# SparkFun_Micro_Temperature_Sensor-STTS22.net
KiCad netlist of a schematic drawn in EAGLE
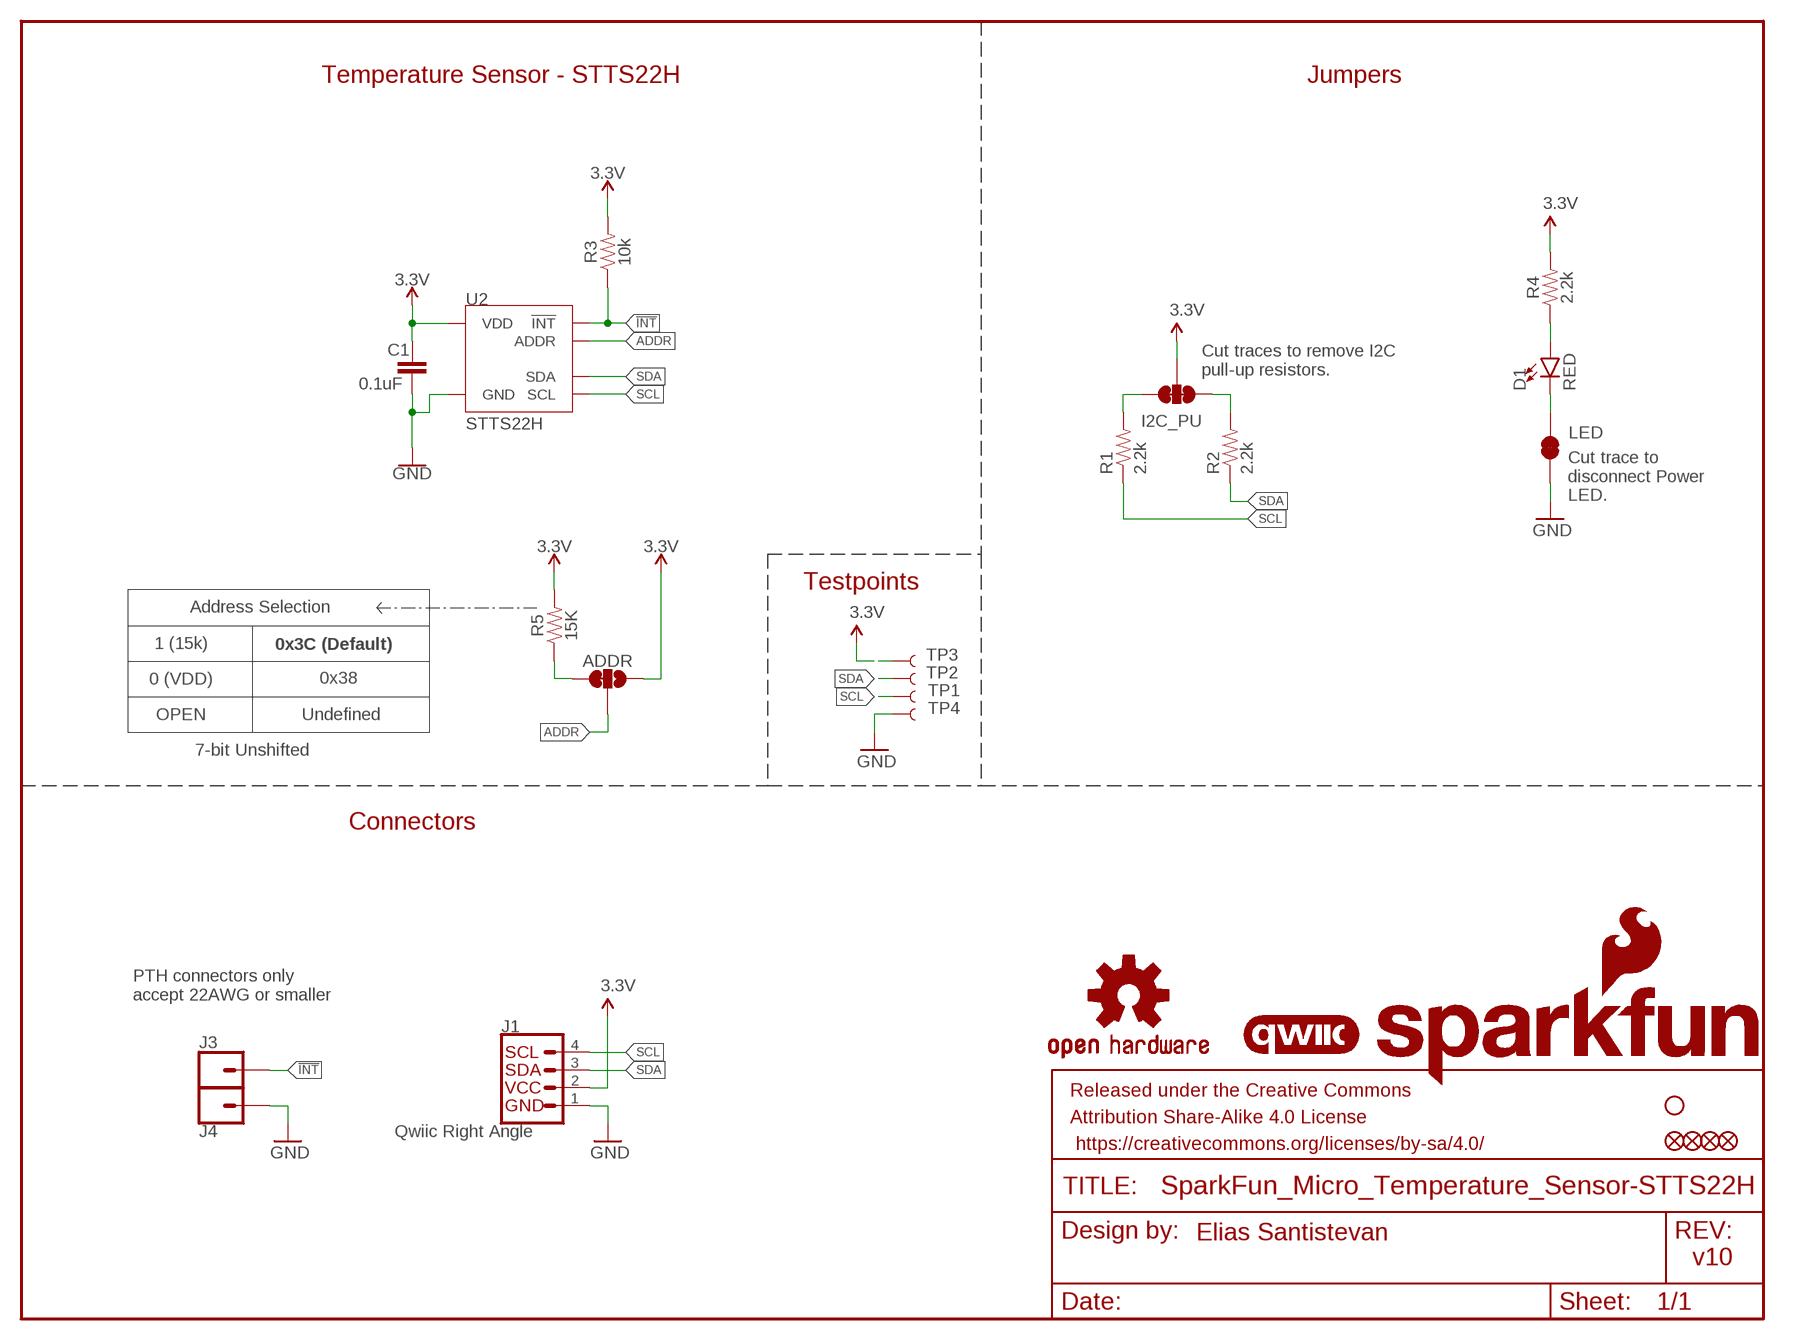
[diagram p0: schematic, sheet 1]

(export (version "E")
  (design (tool "Eeschema 10.0.6"))
  (components
    (comp (ref "ADDR")
      (value "JUMPER-SMT_3_1-NC_TRACE_SILK")
      (footprint "eagle-import:SMT-JUMPER_3_1-NC_TRACE_SILK")
      (libsource (lib "eagle-import") (part "JUMPER-SMT_3_1-NC_TRACE_SILK"))
    )
    (comp (ref "C1")
      (value "0.1uF")
      (footprint "eagle-import:0402-TIGHT")
      (libsource (lib "eagle-import") (part "0.1UF-0402T-16V-10%"))
    )
    (comp (ref "D1")
      (value "RED")
      (footprint "eagle-import:LED-0402")
      (libsource (lib "eagle-import") (part "LED-RED_0402"))
    )
    (comp (ref "FD1")
      (value "FIDUCIALUFIDUCIAL")
      (footprint "eagle-import:FIDUCIAL-MICRO")
      (libsource (lib "eagle-import") (part "FIDUCIALUFIDUCIAL"))
    )
    (comp (ref "FD2")
      (value "FIDUCIALUFIDUCIAL")
      (footprint "eagle-import:FIDUCIAL-MICRO")
      (libsource (lib "eagle-import") (part "FIDUCIALUFIDUCIAL"))
    )
    (comp (ref "FID1")
      (value "FIDUCIALUFIDUCIAL")
      (footprint "eagle-import:FIDUCIAL-MICRO")
      (libsource (lib "eagle-import") (part "FIDUCIALUFIDUCIAL"))
    )
    (comp (ref "FID2")
      (value "FIDUCIALUFIDUCIAL")
      (footprint "eagle-import:FIDUCIAL-MICRO")
      (libsource (lib "eagle-import") (part "FIDUCIALUFIDUCIAL"))
    )
    (comp (ref "FRAME1")
      (value "FRAME-LETTER")
      (footprint "eagle-import:CREATIVE_COMMONS")
      (fields (field (name "DESIGNER") "Elias Santistevan"))
      (libsource (lib "eagle-import") (part "FRAME-LETTER"))
    )
    (comp (ref "I2C_PU")
      (value "S_MODE")
      (footprint "eagle-import:SMT-JUMPER_3_2-NC_TRACE_SILK")
      (libsource (lib "eagle-import") (part "JUMPER-SMT_3_2-NC_TRACE_SILK"))
    )
    (comp (ref "J1")
      (value "Qwiic Right Angle")
      (footprint "eagle-import:JST04_1MM_RA")
      (libsource (lib "eagle-import") (part "I2C_STANDARDQWIIC"))
    )
    (comp (ref "J3")
      (value "CONN_01_1MM")
      (footprint "eagle-import:1X01_1MM_NO_SILK")
      (libsource (lib "eagle-import") (part "CONN_01_1MM"))
    )
    (comp (ref "J4")
      (value "CONN_01_1MM")
      (footprint "eagle-import:1X01_1MM_NO_SILK")
      (libsource (lib "eagle-import") (part "CONN_01_1MM"))
    )
    (comp (ref "LED")
      (value "JUMPER-SMT_2_NC_TRACE_SILK")
      (footprint "eagle-import:SMT-JUMPER_2_NC_TRACE_SILK")
      (libsource (lib "eagle-import") (part "JUMPER-SMT_2_NC_TRACE_SILK"))
    )
    (comp (ref "LOGO1")
      (value "QWIIC_LOGO_3MM")
      (footprint "eagle-import:QWIIC_3MM")
      (libsource (lib "eagle-import") (part "QWIIC_LOGO_3MM"))
    )
    (comp (ref "LOGO2")
      (value "OSHW-LOGOMINI")
      (footprint "eagle-import:OSHW-LOGO-MINI")
      (libsource (lib "eagle-import") (part "OSHW-LOGOMINI"))
    )
    (comp (ref "LOGO3")
      (value "SFE_LOGO_NAME_FLAMEBLANK")
      (footprint "eagle-import:BLANK")
      (libsource (lib "eagle-import") (part "SFE_LOGO_NAME_FLAMEBLANK"))
    )
    (comp (ref "R1")
      (value "2.2k")
      (footprint "eagle-import:0402-TIGHT")
      (libsource (lib "eagle-import") (part "2.2KOHM-0402T-1/16W-1%"))
    )
    (comp (ref "R2")
      (value "2.2k")
      (footprint "eagle-import:0402-TIGHT")
      (libsource (lib "eagle-import") (part "2.2KOHM-0402T-1/16W-1%"))
    )
    (comp (ref "R3")
      (value "10k")
      (footprint "eagle-import:0402-TIGHT")
      (libsource (lib "eagle-import") (part "10KOHM-0402T-1/16W-1%"))
    )
    (comp (ref "R4")
      (value "2.2k")
      (footprint "eagle-import:0402-TIGHT")
      (libsource (lib "eagle-import") (part "2.2KOHM-0402T-1/16W-1%"))
    )
    (comp (ref "R5")
      (value "15K")
      (footprint "eagle-import:0402-TIGHT")
      (libsource (lib "eagle-import") (part "15KOHM-0402-TIGHT-1/16THW-1%"))
    )
    (comp (ref "STANDOFF1")
      (value "STAND-OFFTIGHT")
      (footprint "eagle-import:STAND-OFF-TIGHT")
      (libsource (lib "eagle-import") (part "STAND-OFFTIGHT"))
    )
    (comp (ref "TP1")
      (value "TEST-POINT3")
      (footprint "eagle-import:PAD.03X.03")
      (libsource (lib "eagle-import") (part "TEST-POINT3"))
    )
    (comp (ref "TP2")
      (value "TEST-POINT3")
      (footprint "eagle-import:PAD.03X.03")
      (libsource (lib "eagle-import") (part "TEST-POINT3"))
    )
    (comp (ref "TP3")
      (value "TEST-POINT3")
      (footprint "eagle-import:PAD.03X.03")
      (libsource (lib "eagle-import") (part "TEST-POINT3"))
    )
    (comp (ref "TP4")
      (value "TEST-POINT3")
      (footprint "eagle-import:PAD.03X.03")
      (libsource (lib "eagle-import") (part "TEST-POINT3"))
    )
    (comp (ref "U2")
      (value "STTS22H")
      (footprint "eagle-import:UDFN-6L")
      (libsource (lib "eagle-import") (part "STTS22H"))
    )
  )
  (nets
    (net (code "1") (name "/~{INT}") (class "Default")
      (node (ref "J3") (pin "1") (pinfunction "1_1") (pintype "passive"))
      (node (ref "R3") (pin "1") (pinfunction "1_1") (pintype "passive"))
      (node (ref "U2") (pin "P2") (pinfunction "~{INT}_P2") (pintype "bidirectional"))
    )
    (net (code "2") (name "3.3V") (class "Default")
      (node (ref "ADDR") (pin "1") (pinfunction "1_1") (pintype "passive"))
      (node (ref "C1") (pin "1") (pinfunction "1_1") (pintype "passive"))
      (node (ref "I2C_PU") (pin "2") (pinfunction "2_2") (pintype "passive"))
      (node (ref "J1") (pin "2") (pinfunction "2_2") (pintype "power_in"))
      (node (ref "R3") (pin "2") (pinfunction "2_2") (pintype "passive"))
      (node (ref "R4") (pin "2") (pinfunction "2_2") (pintype "passive"))
      (node (ref "R5") (pin "2") (pinfunction "2_2") (pintype "passive"))
      (node (ref "TP3") (pin "1") (pinfunction "1_1") (pintype "bidirectional"))
      (node (ref "U2") (pin "P3") (pinfunction "VDD_P3") (pintype "power_in"))
    )
    (net (code "3") (name "ADDR") (class "Default")
      (node (ref "ADDR") (pin "2") (pinfunction "2_2") (pintype "passive"))
      (node (ref "U2") (pin "P4") (pinfunction "ADDR_P4") (pintype "bidirectional"))
    )
    (net (code "4") (name "GND") (class "Default")
      (node (ref "C1") (pin "2") (pinfunction "2_2") (pintype "passive"))
      (node (ref "J1") (pin "1") (pinfunction "1_1") (pintype "power_in"))
      (node (ref "J4") (pin "1") (pinfunction "1_1") (pintype "passive"))
      (node (ref "LED") (pin "1") (pinfunction "1_1") (pintype "passive"))
      (node (ref "TP4") (pin "1") (pinfunction "1_1") (pintype "bidirectional"))
      (node (ref "U2") (pin "P5") (pinfunction "GND_P5") (pintype "power_in"))
      (node (ref "U2") (pin "P7") (pinfunction "GND_P7") (pintype "power_in"))
    )
    (net (code "5") (name "Net-(ADDR-Pad3)") (class "Default")
      (node (ref "ADDR") (pin "3") (pinfunction "3_3") (pintype "passive"))
      (node (ref "R5") (pin "1") (pinfunction "1_1") (pintype "passive"))
    )
    (net (code "6") (name "Net-(D1-PadA)") (class "Default")
      (node (ref "D1") (pin "A") (pinfunction "A_A") (pintype "passive"))
      (node (ref "R4") (pin "1") (pinfunction "1_1") (pintype "passive"))
    )
    (net (code "7") (name "Net-(D1-PadC)") (class "Default")
      (node (ref "D1") (pin "C") (pinfunction "C_C") (pintype "passive"))
      (node (ref "LED") (pin "2") (pinfunction "2_2") (pintype "passive"))
    )
    (net (code "8") (name "Net-(I2C_PU-Pad1)") (class "Default")
      (node (ref "I2C_PU") (pin "1") (pinfunction "1_1") (pintype "passive"))
      (node (ref "R1") (pin "2") (pinfunction "2_2") (pintype "passive"))
    )
    (net (code "9") (name "Net-(I2C_PU-Pad3)") (class "Default")
      (node (ref "I2C_PU") (pin "3") (pinfunction "3_3") (pintype "passive"))
      (node (ref "R2") (pin "2") (pinfunction "2_2") (pintype "passive"))
    )
    (net (code "10") (name "SCL") (class "Default")
      (node (ref "J1") (pin "4") (pinfunction "4_4") (pintype "passive"))
      (node (ref "R1") (pin "1") (pinfunction "1_1") (pintype "passive"))
      (node (ref "TP1") (pin "1") (pinfunction "1_1") (pintype "bidirectional"))
      (node (ref "U2") (pin "P1") (pinfunction "SCL_P1") (pintype "bidirectional"))
    )
    (net (code "11") (name "SDA") (class "Default")
      (node (ref "J1") (pin "3") (pinfunction "3_3") (pintype "passive"))
      (node (ref "R2") (pin "1") (pinfunction "1_1") (pintype "passive"))
      (node (ref "TP2") (pin "1") (pinfunction "1_1") (pintype "bidirectional"))
      (node (ref "U2") (pin "P6") (pinfunction "SDA_P6") (pintype "bidirectional"))
    )
  )
)
